# controller.net
KiCad netlist of a schematic drawn in EAGLE
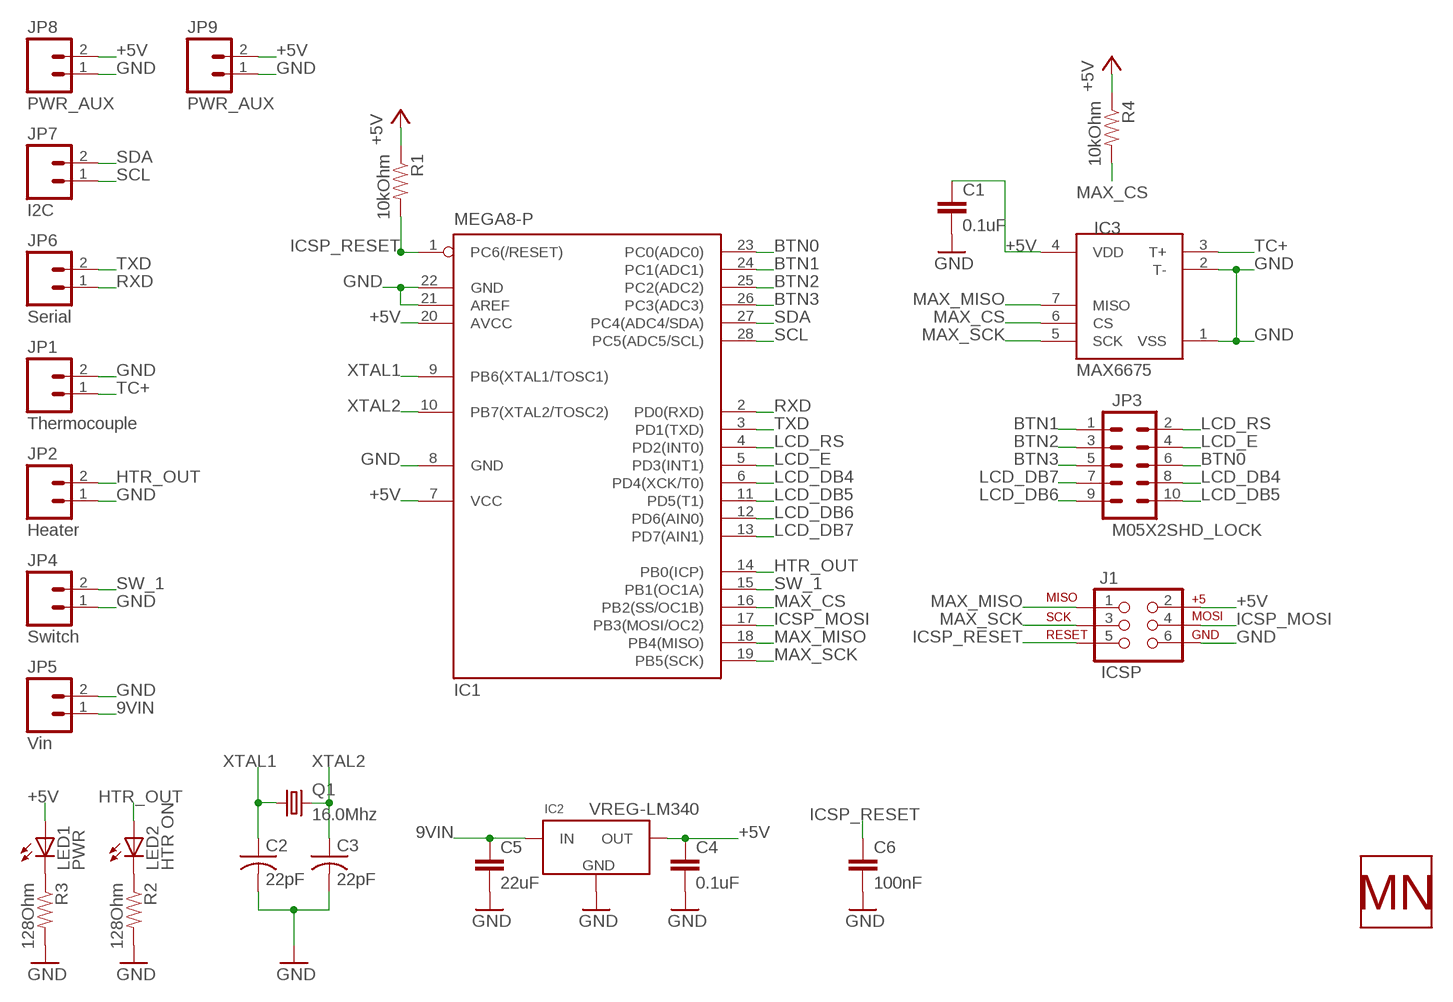
[diagram p0: schematic, sheet 1]

(export (version "E")
  (design (tool "Eeschema 10.0.6"))
  (components
    (comp (ref "C1")
      (value "0.1uF")
      (footprint "eagle-import:CAP-PTH-SMALL")
      (libsource (lib "eagle-import") (part "SparkFun-Passives_CAPPTH"))
    )
    (comp (ref "C2")
      (value "22pF")
      (footprint "eagle-import:C025-030X050")
      (libsource (lib "eagle-import") (part "C-US025-030X050"))
    )
    (comp (ref "C3")
      (value "22pF")
      (footprint "eagle-import:C025-030X050")
      (libsource (lib "eagle-import") (part "C-US025-030X050"))
    )
    (comp (ref "C4")
      (value "0.1uF")
      (footprint "eagle-import:CAP-PTH-SMALL")
      (libsource (lib "eagle-import") (part "SparkFun-Passives_CAPPTH"))
    )
    (comp (ref "C5")
      (value "22uF")
      (footprint "eagle-import:CAP-PTH-5MM")
      (libsource (lib "eagle-import") (part "CAPPTH1"))
    )
    (comp (ref "C6")
      (value "100nF")
      (footprint "eagle-import:0603-CAP")
      (libsource (lib "eagle-import") (part "CAP0603-CAP"))
    )
    (comp (ref "IC1")
      (value "MEGA8-P")
      (footprint "eagle-import:DIL28-3")
      (libsource (lib "eagle-import") (part "MEGA8-P"))
    )
    (comp (ref "IC2")
      (value "VREG-LM340")
      (footprint "eagle-import:D2PACK_A")
      (libsource (lib "eagle-import") (part "VREG-LM340"))
    )
    (comp (ref "IC3")
      (value "MAX6675")
      (footprint "eagle-import:SO08-MAX6675")
      (libsource (lib "eagle-import") (part "MAX6675"))
    )
    (comp (ref "J1")
      (value "ICSP")
      (footprint "eagle-import:2X3")
      (libsource (lib "eagle-import") (part "AVR_SPI_PRG_6PTH"))
    )
    (comp (ref "JP1")
      (value "Thermocouple")
      (footprint "eagle-import:SCREWTERMINAL-5MM-2")
      (libsource (lib "eagle-import") (part "M025MM"))
    )
    (comp (ref "JP2")
      (value "Heater")
      (footprint "eagle-import:SCREWTERMINAL-5MM-2")
      (libsource (lib "eagle-import") (part "M025MM"))
    )
    (comp (ref "JP3")
      (value "M05X2SHD_LOCK")
      (footprint "eagle-import:2X5-SHROUDED_LOCK")
      (libsource (lib "eagle-import") (part "M05X2SHD_LOCK"))
    )
    (comp (ref "JP4")
      (value "Switch")
      (footprint "eagle-import:SCREWTERMINAL-5MM-2")
      (libsource (lib "eagle-import") (part "M025MM"))
    )
    (comp (ref "JP5")
      (value "Vin")
      (footprint "eagle-import:SCREWTERMINAL-5MM-2")
      (libsource (lib "eagle-import") (part "M025MM"))
    )
    (comp (ref "JP6")
      (value "Serial")
      (footprint "eagle-import:1X02")
      (libsource (lib "eagle-import") (part "M02PTH"))
    )
    (comp (ref "JP7")
      (value "I2C")
      (footprint "eagle-import:1X02")
      (libsource (lib "eagle-import") (part "M02PTH"))
    )
    (comp (ref "JP8")
      (value "PWR_AUX")
      (footprint "eagle-import:1X02")
      (libsource (lib "eagle-import") (part "M02PTH"))
    )
    (comp (ref "JP9")
      (value "PWR_AUX")
      (footprint "eagle-import:MOLEX-1X2")
      (libsource (lib "eagle-import") (part "M02POLAR"))
    )
    (comp (ref "LED1")
      (value "PWR")
      (footprint "eagle-import:LED-0603")
      (libsource (lib "eagle-import") (part "LED-GREEN0603"))
    )
    (comp (ref "LED2")
      (value "HTR ON")
      (footprint "eagle-import:LED-0603")
      (fields (field (name "PROD_ID") "DIO-00819"))
      (libsource (lib "eagle-import") (part "LED-RED0603"))
    )
    (comp (ref "Q1")
      (value "16.0Mhz")
      (footprint "eagle-import:HC49_S")
      (libsource (lib "eagle-import") (part "CRYSTALHC49S"))
    )
    (comp (ref "R1")
      (value "10kOhm")
      (footprint "eagle-import:1206")
      (libsource (lib "eagle-import") (part "RESISTOR1206"))
    )
    (comp (ref "R2")
      (value "128Ohm")
      (footprint "eagle-import:1206")
      (libsource (lib "eagle-import") (part "RESISTOR1206"))
    )
    (comp (ref "R3")
      (value "128Ohm")
      (footprint "eagle-import:1206")
      (libsource (lib "eagle-import") (part "RESISTOR1206"))
    )
    (comp (ref "R4")
      (value "10kOhm")
      (footprint "eagle-import:1206")
      (libsource (lib "eagle-import") (part "RESISTOR1206"))
    )
    (comp (ref "U$1")
      (value "MN-LOGO")
      (footprint "eagle-import:MN-LOGO")
      (libsource (lib "eagle-import") (part "MN-LOGO"))
    )
  )
  (nets
    (net (code "1") (name "+5V") (class "Default")
      (node (ref "C1") (pin "1") (pinfunction "1_1") (pintype "passive"))
      (node (ref "C4") (pin "1") (pinfunction "1_1") (pintype "passive"))
      (node (ref "IC1") (pin "20") (pinfunction "AVCC_20") (pintype "power_in"))
      (node (ref "IC1") (pin "7") (pinfunction "VCC_7") (pintype "power_in"))
      (node (ref "IC2") (pin "3") (pinfunction "OUT_3") (pintype "bidirectional"))
      (node (ref "IC3") (pin "4") (pinfunction "VDD_4") (pintype "bidirectional"))
      (node (ref "J1") (pin "2") (pinfunction "2_2") (pintype "passive"))
      (node (ref "JP8") (pin "2") (pinfunction "2_2") (pintype "passive"))
      (node (ref "JP9") (pin "2") (pinfunction "2_2") (pintype "passive"))
      (node (ref "LED1") (pin "A") (pinfunction "A_A") (pintype "passive"))
      (node (ref "R1") (pin "1") (pinfunction "1_1") (pintype "passive"))
      (node (ref "R4") (pin "1") (pinfunction "1_1") (pintype "passive"))
    )
    (net (code "2") (name "/9VIN") (class "Default")
      (node (ref "C5") (pin "1") (pinfunction "1_1") (pintype "passive"))
      (node (ref "IC2") (pin "1") (pinfunction "IN_1") (pintype "bidirectional"))
      (node (ref "JP5") (pin "1") (pinfunction "1_1") (pintype "passive"))
    )
    (net (code "3") (name "/BTN0") (class "Default")
      (node (ref "IC1") (pin "23") (pinfunction "PC0(ADC0)_23") (pintype "bidirectional"))
      (node (ref "JP3") (pin "6") (pinfunction "6_6") (pintype "passive"))
    )
    (net (code "4") (name "/BTN1") (class "Default")
      (node (ref "IC1") (pin "24") (pinfunction "PC1(ADC1)_24") (pintype "bidirectional"))
      (node (ref "JP3") (pin "1") (pinfunction "1_1") (pintype "passive"))
    )
    (net (code "5") (name "/BTN2") (class "Default")
      (node (ref "IC1") (pin "25") (pinfunction "PC2(ADC2)_25") (pintype "bidirectional"))
      (node (ref "JP3") (pin "3") (pinfunction "3_3") (pintype "passive"))
    )
    (net (code "6") (name "/BTN3") (class "Default")
      (node (ref "IC1") (pin "26") (pinfunction "PC3(ADC3)_26") (pintype "bidirectional"))
      (node (ref "JP3") (pin "5") (pinfunction "5_5") (pintype "passive"))
    )
    (net (code "7") (name "/HTR_OUT") (class "Default")
      (node (ref "IC1") (pin "14") (pinfunction "PB0(ICP)_14") (pintype "bidirectional"))
      (node (ref "JP2") (pin "2") (pinfunction "2_2") (pintype "passive"))
      (node (ref "LED2") (pin "A") (pinfunction "A_A") (pintype "passive"))
    )
    (net (code "8") (name "/ICSP_MOSI") (class "Default")
      (node (ref "IC1") (pin "17") (pinfunction "PB3(MOSI/OC2)_17") (pintype "bidirectional"))
      (node (ref "J1") (pin "4") (pinfunction "4_4") (pintype "passive"))
    )
    (net (code "9") (name "/ICSP_RESET") (class "Default")
      (node (ref "C6") (pin "1") (pinfunction "1_1") (pintype "passive"))
      (node (ref "IC1") (pin "1") (pinfunction "PC6(/RESET)_1") (pintype "bidirectional"))
      (node (ref "J1") (pin "5") (pinfunction "5_5") (pintype "passive"))
      (node (ref "R1") (pin "2") (pinfunction "2_2") (pintype "passive"))
    )
    (net (code "10") (name "/LCD_DB4") (class "Default")
      (node (ref "IC1") (pin "6") (pinfunction "PD4(XCK/T0)_6") (pintype "bidirectional"))
      (node (ref "JP3") (pin "8") (pinfunction "8_8") (pintype "passive"))
    )
    (net (code "11") (name "/LCD_DB5") (class "Default")
      (node (ref "IC1") (pin "11") (pinfunction "PD5(T1)_11") (pintype "bidirectional"))
      (node (ref "JP3") (pin "10") (pinfunction "10_10") (pintype "passive"))
    )
    (net (code "12") (name "/LCD_DB6") (class "Default")
      (node (ref "IC1") (pin "12") (pinfunction "PD6(AIN0)_12") (pintype "bidirectional"))
      (node (ref "JP3") (pin "9") (pinfunction "9_9") (pintype "passive"))
    )
    (net (code "13") (name "/LCD_DB7") (class "Default")
      (node (ref "IC1") (pin "13") (pinfunction "PD7(AIN1)_13") (pintype "bidirectional"))
      (node (ref "JP3") (pin "7") (pinfunction "7_7") (pintype "passive"))
    )
    (net (code "14") (name "/LCD_E") (class "Default")
      (node (ref "IC1") (pin "5") (pinfunction "PD3(INT1)_5") (pintype "bidirectional"))
      (node (ref "JP3") (pin "4") (pinfunction "4_4") (pintype "passive"))
    )
    (net (code "15") (name "/LCD_RS") (class "Default")
      (node (ref "IC1") (pin "4") (pinfunction "PD2(INT0)_4") (pintype "bidirectional"))
      (node (ref "JP3") (pin "2") (pinfunction "2_2") (pintype "passive"))
    )
    (net (code "16") (name "/MAX_CS") (class "Default")
      (node (ref "IC1") (pin "16") (pinfunction "PB2(SS/OC1B)_16") (pintype "bidirectional"))
      (node (ref "IC3") (pin "6") (pinfunction "CS_6") (pintype "bidirectional"))
      (node (ref "R4") (pin "2") (pinfunction "2_2") (pintype "passive"))
    )
    (net (code "17") (name "/MAX_MISO") (class "Default")
      (node (ref "IC1") (pin "18") (pinfunction "PB4(MISO)_18") (pintype "bidirectional"))
      (node (ref "IC3") (pin "7") (pinfunction "MISO_7") (pintype "bidirectional"))
      (node (ref "J1") (pin "1") (pinfunction "1_1") (pintype "passive"))
    )
    (net (code "18") (name "/MAX_SCK") (class "Default")
      (node (ref "IC1") (pin "19") (pinfunction "PB5(SCK)_19") (pintype "bidirectional"))
      (node (ref "IC3") (pin "5") (pinfunction "SCK_5") (pintype "bidirectional"))
      (node (ref "J1") (pin "3") (pinfunction "3_3") (pintype "passive"))
    )
    (net (code "19") (name "/RXD") (class "Default")
      (node (ref "IC1") (pin "2") (pinfunction "PD0(RXD)_2") (pintype "bidirectional"))
      (node (ref "JP6") (pin "1") (pinfunction "1_1") (pintype "passive"))
    )
    (net (code "20") (name "/SCL") (class "Default")
      (node (ref "IC1") (pin "28") (pinfunction "PC5(ADC5/SCL)_28") (pintype "bidirectional"))
      (node (ref "JP7") (pin "1") (pinfunction "1_1") (pintype "passive"))
    )
    (net (code "21") (name "/SDA") (class "Default")
      (node (ref "IC1") (pin "27") (pinfunction "PC4(ADC4/SDA)_27") (pintype "bidirectional"))
      (node (ref "JP7") (pin "2") (pinfunction "2_2") (pintype "passive"))
    )
    (net (code "22") (name "/SW_1") (class "Default")
      (node (ref "IC1") (pin "15") (pinfunction "PB1(OC1A)_15") (pintype "bidirectional"))
      (node (ref "JP4") (pin "2") (pinfunction "2_2") (pintype "passive"))
    )
    (net (code "23") (name "/TC+") (class "Default")
      (node (ref "IC3") (pin "3") (pinfunction "T+_3") (pintype "bidirectional"))
      (node (ref "JP1") (pin "1") (pinfunction "1_1") (pintype "passive"))
    )
    (net (code "24") (name "/TXD") (class "Default")
      (node (ref "IC1") (pin "3") (pinfunction "PD1(TXD)_3") (pintype "bidirectional"))
      (node (ref "JP6") (pin "2") (pinfunction "2_2") (pintype "passive"))
    )
    (net (code "25") (name "/XTAL1") (class "Default")
      (node (ref "C2") (pin "1") (pinfunction "1_1") (pintype "passive"))
      (node (ref "IC1") (pin "9") (pinfunction "PB6(XTAL1/TOSC1)_9") (pintype "bidirectional"))
      (node (ref "Q1") (pin "1") (pinfunction "1_1") (pintype "passive"))
    )
    (net (code "26") (name "/XTAL2") (class "Default")
      (node (ref "C3") (pin "1") (pinfunction "1_1") (pintype "passive"))
      (node (ref "IC1") (pin "10") (pinfunction "PB7(XTAL2/TOSC2)_10") (pintype "bidirectional"))
      (node (ref "Q1") (pin "2") (pinfunction "2_2") (pintype "passive"))
    )
    (net (code "27") (name "GND") (class "Default")
      (node (ref "C1") (pin "2") (pinfunction "2_2") (pintype "passive"))
      (node (ref "C2") (pin "2") (pinfunction "2_2") (pintype "passive"))
      (node (ref "C3") (pin "2") (pinfunction "2_2") (pintype "passive"))
      (node (ref "C4") (pin "2") (pinfunction "2_2") (pintype "passive"))
      (node (ref "C5") (pin "2") (pinfunction "2_2") (pintype "passive"))
      (node (ref "C6") (pin "2") (pinfunction "2_2") (pintype "passive"))
      (node (ref "IC1") (pin "21") (pinfunction "AREF_21") (pintype "passive"))
      (node (ref "IC1") (pin "22") (pinfunction "GND_22") (pintype "power_in"))
      (node (ref "IC1") (pin "8") (pinfunction "GND_8") (pintype "power_in"))
      (node (ref "IC2") (pin "2") (pinfunction "GND_2") (pintype "bidirectional"))
      (node (ref "IC2") (pin "TAB") (pinfunction "GND_TAB") (pintype "bidirectional"))
      (node (ref "IC3") (pin "1") (pinfunction "VSS_1") (pintype "bidirectional"))
      (node (ref "IC3") (pin "2") (pinfunction "T-_2") (pintype "bidirectional"))
      (node (ref "J1") (pin "6") (pinfunction "6_6") (pintype "passive"))
      (node (ref "JP1") (pin "2") (pinfunction "2_2") (pintype "passive"))
      (node (ref "JP2") (pin "1") (pinfunction "1_1") (pintype "passive"))
      (node (ref "JP4") (pin "1") (pinfunction "1_1") (pintype "passive"))
      (node (ref "JP5") (pin "2") (pinfunction "2_2") (pintype "passive"))
      (node (ref "JP8") (pin "1") (pinfunction "1_1") (pintype "passive"))
      (node (ref "JP9") (pin "1") (pinfunction "1_1") (pintype "passive"))
      (node (ref "R2") (pin "2") (pinfunction "2_2") (pintype "passive"))
      (node (ref "R3") (pin "2") (pinfunction "2_2") (pintype "passive"))
    )
    (net (code "28") (name "Net-(LED1-PadC)") (class "Default")
      (node (ref "LED1") (pin "C") (pinfunction "C_C") (pintype "passive"))
      (node (ref "R3") (pin "1") (pinfunction "1_1") (pintype "passive"))
    )
    (net (code "29") (name "Net-(LED2-PadC)") (class "Default")
      (node (ref "LED2") (pin "C") (pinfunction "C_C") (pintype "passive"))
      (node (ref "R2") (pin "1") (pinfunction "1_1") (pintype "passive"))
    )
  )
)
